# 130618_I_T_V_AriloRX_0_0.net
KiCad netlist of a schematic drawn in EAGLE
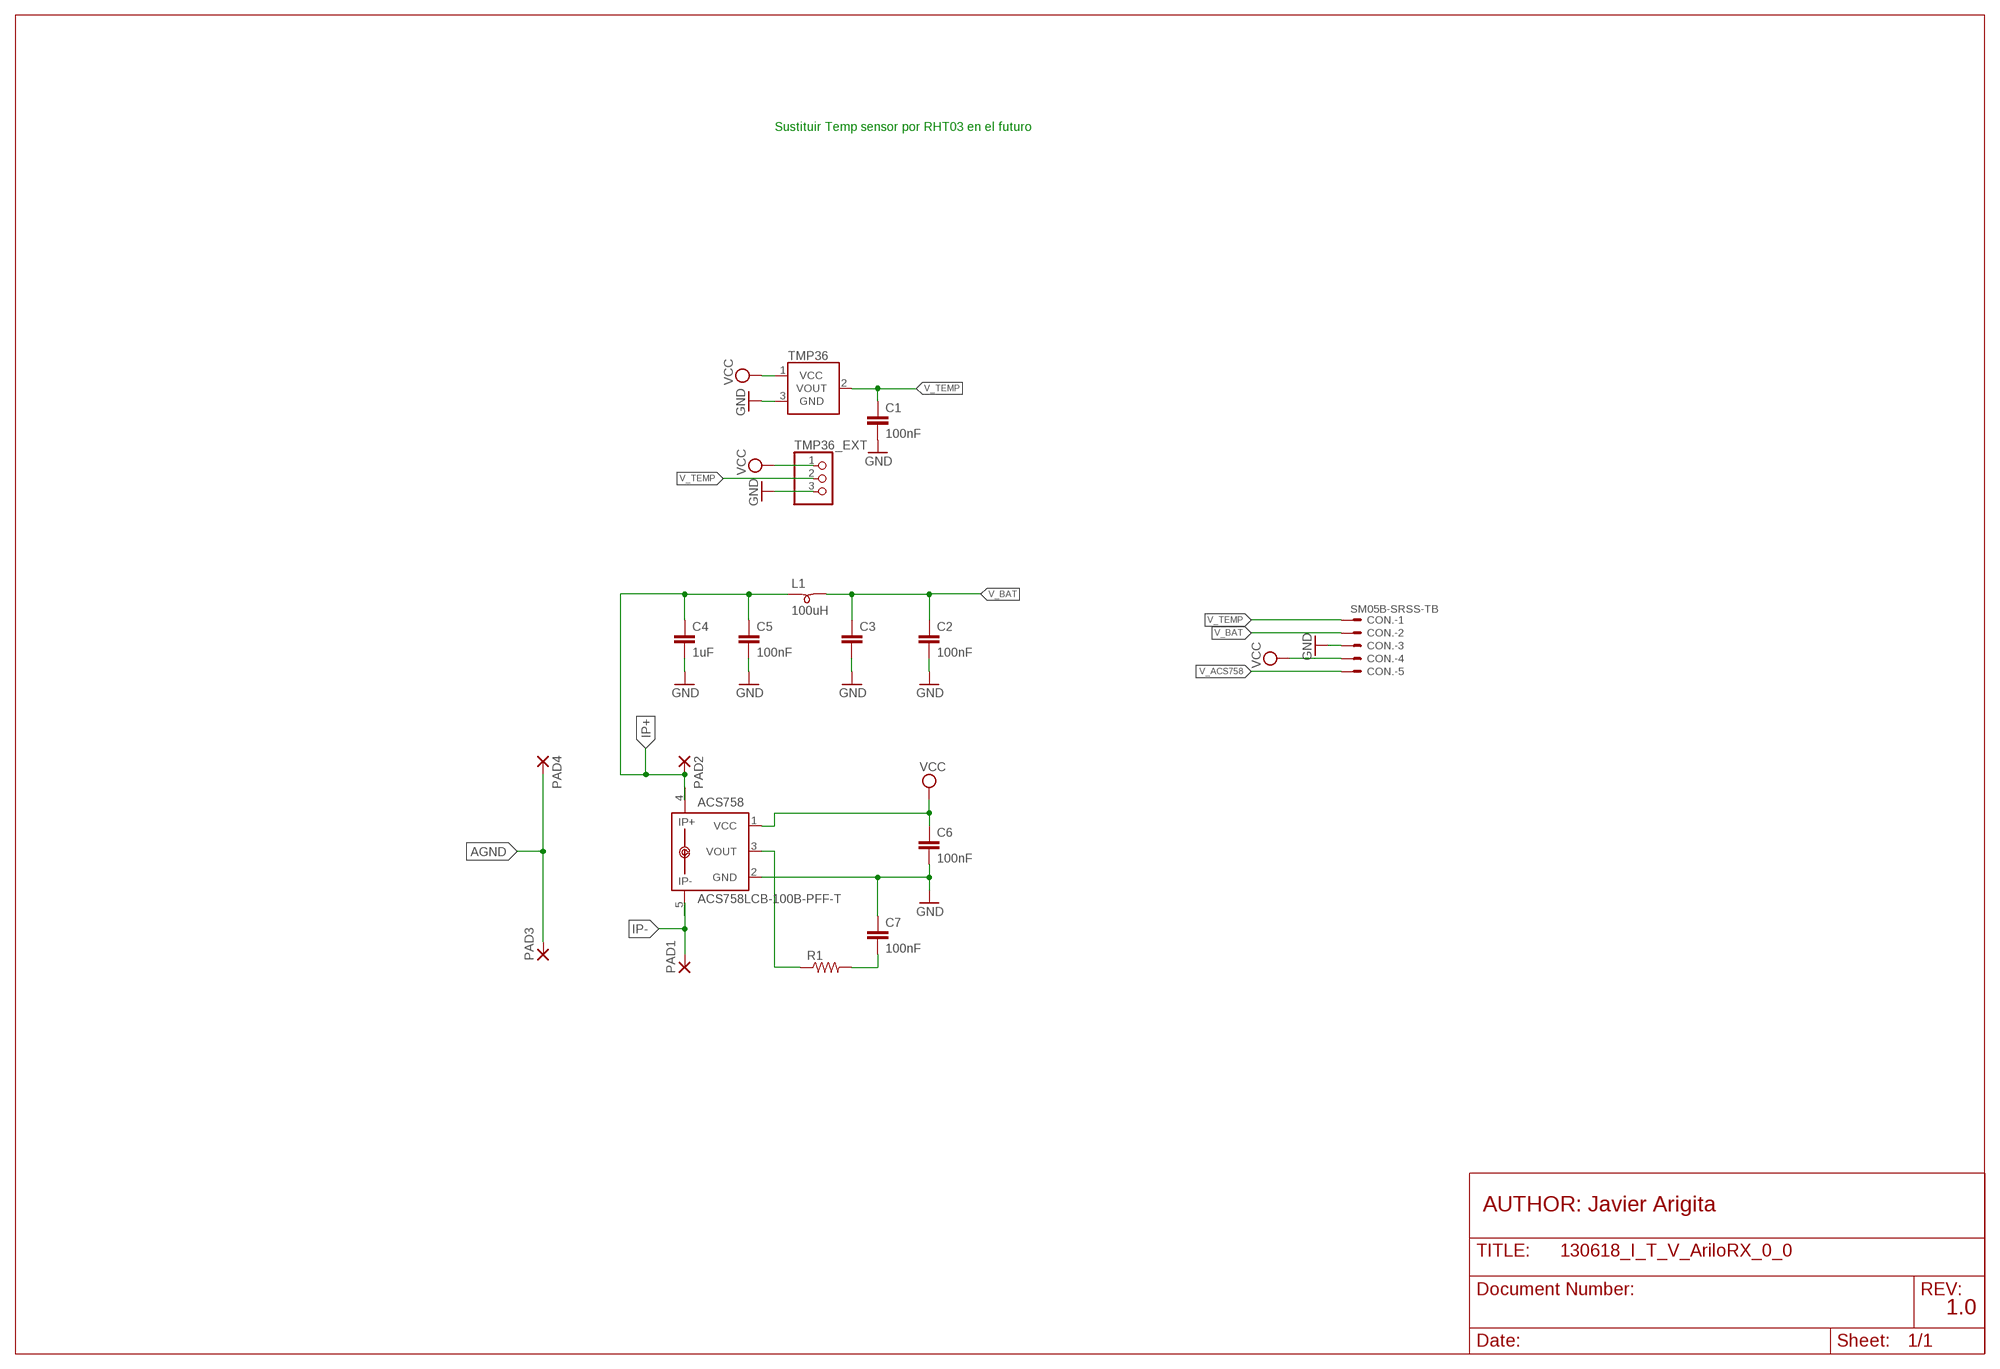
[diagram p0: schematic, sheet 1]

(export (version "E")
  (design (tool "Eeschema 10.0.6"))
  (components
    (comp (ref "ACS758")
      (value "ACS758LCB-100B-PFF-T")
      (footprint "eagle-import:CB-PFF")
      (libsource (lib "eagle-import") (part "ACS758LCB-100B-PFF-T"))
    )
    (comp (ref "C1")
      (value "100nF")
      (footprint "eagle-import:C0805")
      (libsource (lib "eagle-import") (part "C-EUC0805"))
    )
    (comp (ref "C2")
      (value "100nF")
      (footprint "eagle-import:C0805")
      (libsource (lib "eagle-import") (part "C-EUC0805"))
    )
    (comp (ref "C3")
      (value "C-EUC3216")
      (footprint "eagle-import:C3216")
      (libsource (lib "eagle-import") (part "C-EUC3216"))
    )
    (comp (ref "C4")
      (value "1uF")
      (footprint "eagle-import:C3216")
      (libsource (lib "eagle-import") (part "C-EUC3216"))
    )
    (comp (ref "C5")
      (value "100nF")
      (footprint "eagle-import:C0805")
      (libsource (lib "eagle-import") (part "C-EUC0805"))
    )
    (comp (ref "C6")
      (value "100nF")
      (footprint "eagle-import:C0805")
      (libsource (lib "eagle-import") (part "C-EUC0805"))
    )
    (comp (ref "C7")
      (value "100nF")
      (footprint "eagle-import:C0805")
      (libsource (lib "eagle-import") (part "C-EUC0805"))
    )
    (comp (ref "CON.")
      (value "SM05B-SRSS-TB")
      (footprint "eagle-import:SM05B-SRSS-TB")
      (libsource (lib "eagle-import") (part "?M05B-SRSS-TBS"))
    )
    (comp (ref "L1")
      (value "100uH")
      (footprint "eagle-import:SM-B5")
      (libsource (lib "eagle-import") (part "SM-B5"))
    )
    (comp (ref "PAD1")
      (value "SMD5")
      (footprint "eagle-import:SMD2,54-5,08")
      (libsource (lib "eagle-import") (part "SMD5"))
    )
    (comp (ref "PAD2")
      (value "SMD5")
      (footprint "eagle-import:SMD2,54-5,08")
      (libsource (lib "eagle-import") (part "SMD5"))
    )
    (comp (ref "PAD3")
      (value "SMD5")
      (footprint "eagle-import:SMD2,54-5,08")
      (libsource (lib "eagle-import") (part "SMD5"))
    )
    (comp (ref "PAD4")
      (value "SMD5")
      (footprint "eagle-import:SMD2,54-5,08")
      (libsource (lib "eagle-import") (part "SMD5"))
    )
    (comp (ref "R1")
      (value "RESISTOR0805")
      (footprint "eagle-import:R0805")
      (libsource (lib "eagle-import") (part "RESISTOR0805"))
    )
    (comp (ref "TMP36")
      (value "TMP36GT9")
      (footprint "eagle-import:TO-92")
      (libsource (lib "eagle-import") (part "TMP36GT9"))
    )
    (comp (ref "TMP36_EXT")
      (value "PINHD-1X3")
      (footprint "eagle-import:1X03")
      (libsource (lib "eagle-import") (part "PINHD-1X3"))
    )
  )
  (nets
    (net (code "1") (name "AGND") (class "Default")
      (node (ref "PAD3") (pin "1") (pinfunction "P_1") (pintype "passive"))
      (node (ref "PAD4") (pin "1") (pinfunction "P_1") (pintype "passive"))
    )
    (net (code "2") (name "GND") (class "Default")
      (node (ref "ACS758") (pin "2") (pinfunction "GND_2") (pintype "power_in"))
      (node (ref "C1") (pin "2") (pinfunction "2_2") (pintype "passive"))
      (node (ref "C2") (pin "2") (pinfunction "2_2") (pintype "passive"))
      (node (ref "C3") (pin "2") (pinfunction "2_2") (pintype "passive"))
      (node (ref "C4") (pin "2") (pinfunction "2_2") (pintype "passive"))
      (node (ref "C5") (pin "2") (pinfunction "2_2") (pintype "passive"))
      (node (ref "C6") (pin "2") (pinfunction "2_2") (pintype "passive"))
      (node (ref "C7") (pin "1") (pinfunction "1_1") (pintype "passive"))
      (node (ref "CON.") (pin "3") (pinfunction "S_3") (pintype "passive"))
      (node (ref "TMP36") (pin "3") (pinfunction "GND_3") (pintype "bidirectional"))
      (node (ref "TMP36_EXT") (pin "3") (pinfunction "3_3") (pintype "passive"))
    )
    (net (code "3") (name "IP+") (class "Default")
      (node (ref "ACS758") (pin "4") (pinfunction "IP+_4") (pintype "passive"))
      (node (ref "ACS758") (pin "IP+1") (pinfunction "IP+1_IP+1") (pintype "input"))
      (node (ref "C4") (pin "1") (pinfunction "1_1") (pintype "passive"))
      (node (ref "C5") (pin "1") (pinfunction "1_1") (pintype "passive"))
      (node (ref "L1") (pin "1") (pinfunction "1_1") (pintype "passive"))
      (node (ref "PAD2") (pin "1") (pinfunction "P_1") (pintype "passive"))
    )
    (net (code "4") (name "IP-") (class "Default")
      (node (ref "ACS758") (pin "5") (pinfunction "IP-_5") (pintype "passive"))
      (node (ref "ACS758") (pin "IP-1") (pinfunction "IP-1_IP-1") (pintype "input"))
      (node (ref "PAD1") (pin "1") (pinfunction "P_1") (pintype "passive"))
    )
    (net (code "5") (name "Net-(ACS758-VOUT)") (class "Default")
      (node (ref "ACS758") (pin "3") (pinfunction "VOUT_3") (pintype "output"))
      (node (ref "R1") (pin "1") (pinfunction "1_1") (pintype "passive"))
    )
    (net (code "6") (name "Net-(C7-Pad2)") (class "Default")
      (node (ref "C7") (pin "2") (pinfunction "2_2") (pintype "passive"))
      (node (ref "R1") (pin "2") (pinfunction "2_2") (pintype "passive"))
    )
    (net (code "7") (name "VCC") (class "Default")
      (node (ref "ACS758") (pin "1") (pinfunction "VCC_1") (pintype "power_in"))
      (node (ref "C6") (pin "1") (pinfunction "1_1") (pintype "passive"))
      (node (ref "CON.") (pin "4") (pinfunction "S_4") (pintype "passive"))
      (node (ref "TMP36") (pin "1") (pinfunction "VCC_1") (pintype "bidirectional"))
      (node (ref "TMP36_EXT") (pin "1") (pinfunction "1_1") (pintype "passive"))
    )
    (net (code "8") (name "V_ACS758") (class "Default")
      (node (ref "CON.") (pin "5") (pinfunction "S_5") (pintype "passive"))
    )
    (net (code "9") (name "V_BAT") (class "Default")
      (node (ref "C2") (pin "1") (pinfunction "1_1") (pintype "passive"))
      (node (ref "C3") (pin "1") (pinfunction "1_1") (pintype "passive"))
      (node (ref "CON.") (pin "2") (pinfunction "S_2") (pintype "passive"))
      (node (ref "L1") (pin "2") (pinfunction "2_2") (pintype "passive"))
    )
    (net (code "10") (name "V_TEMP") (class "Default")
      (node (ref "C1") (pin "1") (pinfunction "1_1") (pintype "passive"))
      (node (ref "CON.") (pin "1") (pinfunction "S_1") (pintype "passive"))
      (node (ref "TMP36") (pin "2") (pinfunction "VOUT_2") (pintype "bidirectional"))
      (node (ref "TMP36_EXT") (pin "2") (pinfunction "2_2") (pintype "passive"))
    )
  )
)
